# tl.net
KiCad netlist of a schematic drawn in Altium Designer
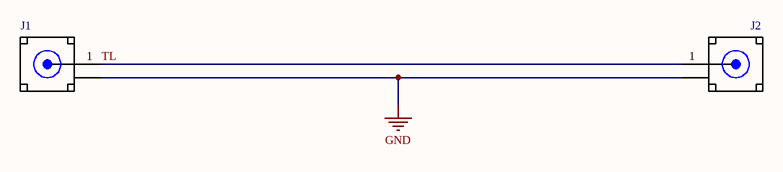
[diagram p0: tl.SchDoc]

(export (version "E")
  (design (tool "Eeschema 10.0.6"))
  (components
    (comp (ref "J1")
      (value "SMA-J-P-H-ST-EM1")
      (footprint "SAMTEC SMA-J-P-H-ST-EM1")
      (description "CONN SMA JACK STR 50OHM EDGE MNT")
      (fields (field (name "MANUFACTURER") "Samtec Inc."))
      (libsource (lib "Generic Altium Database") (part "SAMTEC SMA-J-P-H-ST-EM1"))
    )
    (comp (ref "J2")
      (value "SMA-J-P-H-ST-EM1")
      (footprint "SAMTEC SMA-J-P-H-ST-EM1")
      (description "CONN SMA JACK STR 50OHM EDGE MNT")
      (fields (field (name "MANUFACTURER") "Samtec Inc."))
      (libsource (lib "Generic Altium Database") (part "SAMTEC SMA-J-P-H-ST-EM1"))
    )
  )
  (nets
    (net (code "1") (name "/TL") (class "Default")
      (node (ref "J1") (pin "1") (pinfunction "SIGNAL_1") (pintype "passive"))
      (node (ref "J2") (pin "1") (pinfunction "SIGNAL_1") (pintype "passive"))
    )
    (net (code "2") (name "GND") (class "Default")
      (node (ref "J1") (pin "2") (pinfunction "GND_2") (pintype "power_in"))
      (node (ref "J2") (pin "2") (pinfunction "GND_2") (pintype "power_in"))
    )
  )
)
